# Sensor_Glove_Sensors-X02.net
KiCad netlist of a schematic drawn in Altium Designer
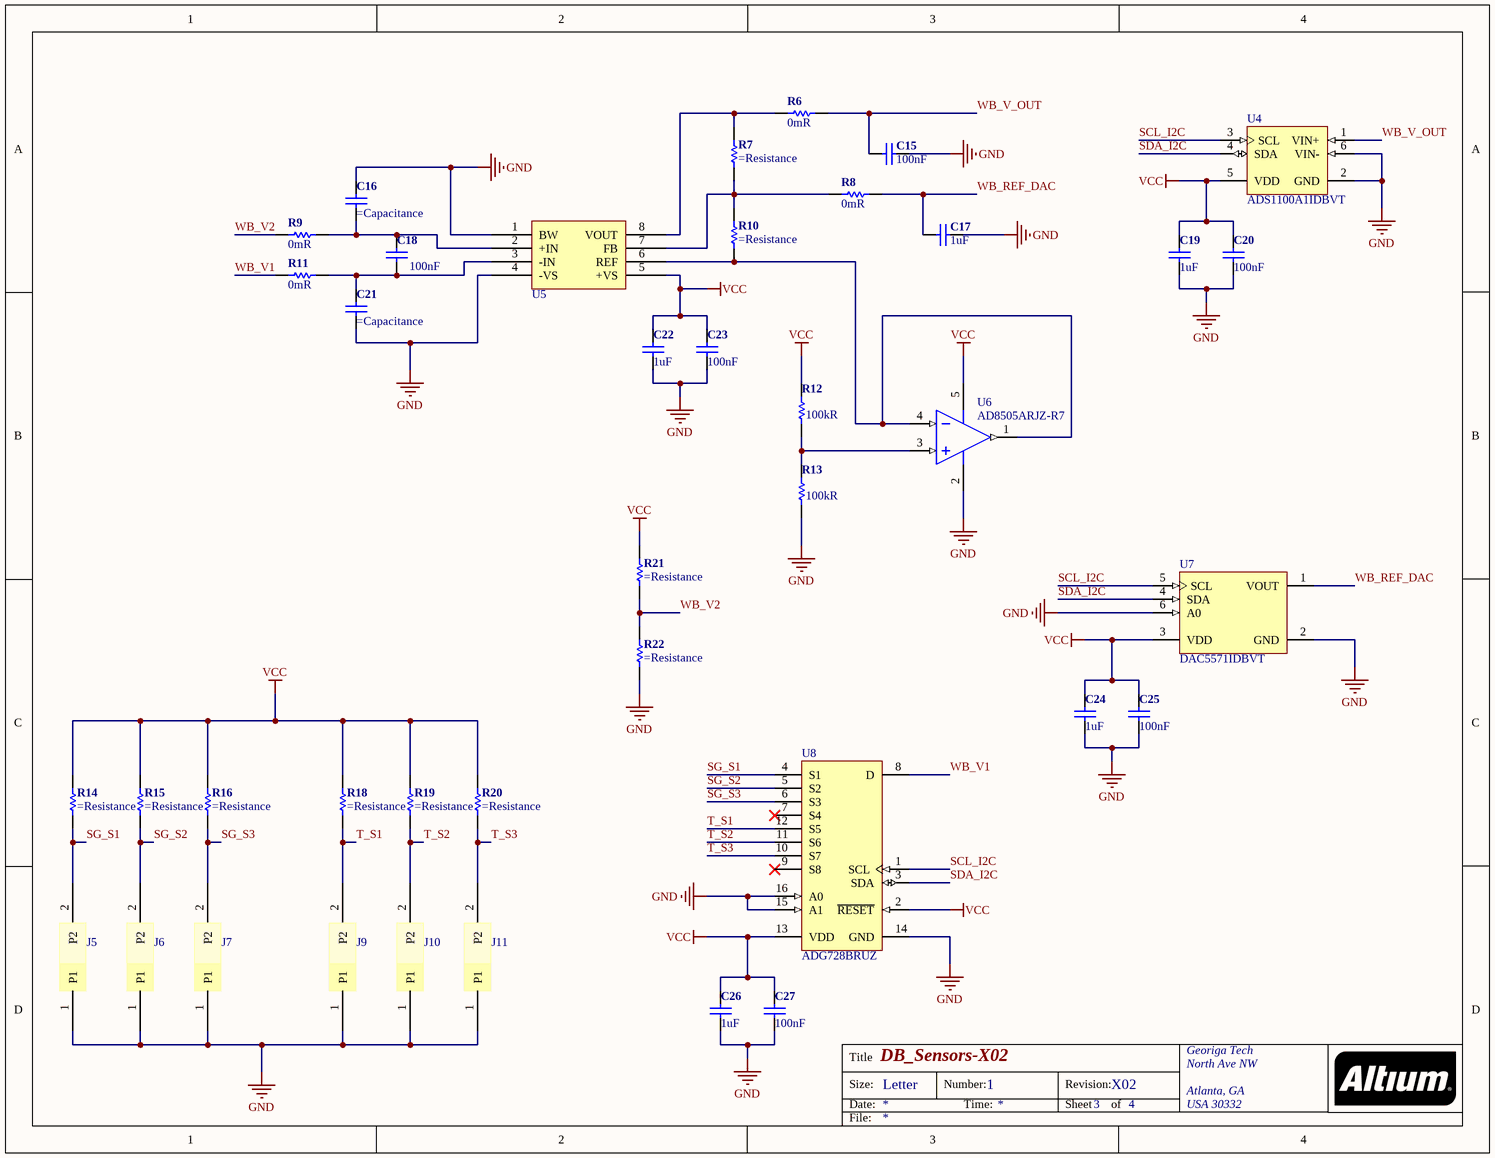
[diagram p0: Sensor_Glove_Sensors-X02.SchDoc]

(export (version "E")
  (design (tool "Eeschema 10.0.6"))
  (components
    (comp (ref "C15")
      (value "100nF")
      (footprint "C0402")
      (fields
        (field (name "MANUFACTURER") "Taiyo Yuden")
        (field (name "MANUFACTURER PART NUMBER") "TMK105BJ104KV-F")
        (field (name "TOLERANCE") "10%")
      )
      (libsource (lib "DB-X02") (part "C-0402(1005)"))
    )
    (comp (ref "C16")
      (value "~")
      (footprint "C0402")
      (description "___ OHM ___ mW 0402(1005) SMD")
      (libsource (lib "DB-X02") (part "C-0402(1005)"))
    )
    (comp (ref "C17")
      (value "1uF")
      (footprint "C0402")
      (fields
        (field (name "MANUFACTURER") "Yageo")
        (field (name "MANUFACTURER PART NUMBER") "CC0402MRX5R5BB105")
        (field (name "TOLERANCE") "20%")
      )
      (libsource (lib "DB-X02") (part "C-0402(1005)"))
    )
    (comp (ref "C18")
      (value "100nF")
      (footprint "C0402")
      (fields
        (field (name "MANUFACTURER") "Taiyo Yuden")
        (field (name "MANUFACTURER PART NUMBER") "TMK105BJ104KV-F")
        (field (name "TOLERANCE") "10%")
      )
      (libsource (lib "DB-X02") (part "C-0402(1005)"))
    )
    (comp (ref "C19")
      (value "1uF")
      (footprint "C0402")
      (fields
        (field (name "MANUFACTURER") "Yageo")
        (field (name "MANUFACTURER PART NUMBER") "CC0402MRX5R5BB105")
        (field (name "TOLERANCE") "20%")
      )
      (libsource (lib "DB-X02") (part "C-0402(1005)"))
    )
    (comp (ref "C20")
      (value "100nF")
      (footprint "C0402")
      (fields
        (field (name "MANUFACTURER") "Taiyo Yuden")
        (field (name "MANUFACTURER PART NUMBER") "TMK105BJ104KV-F")
        (field (name "TOLERANCE") "10%")
      )
      (libsource (lib "DB-X02") (part "C-0402(1005)"))
    )
    (comp (ref "C21")
      (value "~")
      (footprint "C0402")
      (description "___ OHM ___ mW 0402(1005) SMD")
      (libsource (lib "DB-X02") (part "C-0402(1005)"))
    )
    (comp (ref "C22")
      (value "1uF")
      (footprint "C0402")
      (fields
        (field (name "MANUFACTURER") "Yageo")
        (field (name "MANUFACTURER PART NUMBER") "CC0402MRX5R5BB105")
        (field (name "TOLERANCE") "20%")
      )
      (libsource (lib "DB-X02") (part "C-0402(1005)"))
    )
    (comp (ref "C23")
      (value "100nF")
      (footprint "C0402")
      (fields
        (field (name "MANUFACTURER") "Taiyo Yuden")
        (field (name "MANUFACTURER PART NUMBER") "TMK105BJ104KV-F")
        (field (name "TOLERANCE") "10%")
      )
      (libsource (lib "DB-X02") (part "C-0402(1005)"))
    )
    (comp (ref "C24")
      (value "1uF")
      (footprint "C0402")
      (fields
        (field (name "MANUFACTURER") "Yageo")
        (field (name "MANUFACTURER PART NUMBER") "CC0402MRX5R5BB105")
        (field (name "TOLERANCE") "20%")
      )
      (libsource (lib "DB-X02") (part "C-0402(1005)"))
    )
    (comp (ref "C25")
      (value "100nF")
      (footprint "C0402")
      (fields
        (field (name "MANUFACTURER") "Taiyo Yuden")
        (field (name "MANUFACTURER PART NUMBER") "TMK105BJ104KV-F")
        (field (name "TOLERANCE") "10%")
      )
      (libsource (lib "DB-X02") (part "C-0402(1005)"))
    )
    (comp (ref "C26")
      (value "1uF")
      (footprint "C0402")
      (fields
        (field (name "MANUFACTURER") "Yageo")
        (field (name "MANUFACTURER PART NUMBER") "CC0402MRX5R5BB105")
        (field (name "TOLERANCE") "20%")
      )
      (libsource (lib "DB-X02") (part "C-0402(1005)"))
    )
    (comp (ref "C27")
      (value "100nF")
      (footprint "C0402")
      (fields
        (field (name "MANUFACTURER") "Taiyo Yuden")
        (field (name "MANUFACTURER PART NUMBER") "TMK105BJ104KV-F")
        (field (name "TOLERANCE") "10%")
      )
      (libsource (lib "DB-X02") (part "C-0402(1005)"))
    )
    (comp (ref "J5")
      (value "Sensor Interconnect Pads")
      (footprint "Sensor_Interconnect_Pad")
      (description "Hole Pads for sensor interconnect solder pads")
      (libsource (lib "Sensor_Glove-X02") (part "Sensor_Interconnect"))
    )
    (comp (ref "J6")
      (value "Sensor Interconnect Pads")
      (footprint "Sensor_Interconnect_Pad")
      (description "Hole Pads for sensor interconnect solder pads")
      (libsource (lib "Sensor_Glove-X02") (part "Sensor_Interconnect"))
    )
    (comp (ref "J7")
      (value "Sensor Interconnect Pads")
      (footprint "Sensor_Interconnect_Pad")
      (description "Hole Pads for sensor interconnect solder pads")
      (libsource (lib "Sensor_Glove-X02") (part "Sensor_Interconnect"))
    )
    (comp (ref "J9")
      (value "Sensor Interconnect Pads")
      (footprint "Sensor_Interconnect_Pad")
      (description "Hole Pads for sensor interconnect solder pads")
      (libsource (lib "Sensor_Glove-X02") (part "Sensor_Interconnect"))
    )
    (comp (ref "J10")
      (value "Sensor Interconnect Pads")
      (footprint "Sensor_Interconnect_Pad")
      (description "Hole Pads for sensor interconnect solder pads")
      (libsource (lib "Sensor_Glove-X02") (part "Sensor_Interconnect"))
    )
    (comp (ref "J11")
      (value "Sensor Interconnect Pads")
      (footprint "Sensor_Interconnect_Pad")
      (description "Hole Pads for sensor interconnect solder pads")
      (libsource (lib "Sensor_Glove-X02") (part "Sensor_Interconnect"))
    )
    (comp (ref "R6")
      (value "0mR")
      (footprint "R0402")
      (description "Fixed Resistor, Metal Glaze/thick Film, 0.0625W, 0ohm, Surface Mount, 0402")
      (fields
        (field (name "MANUFACTURER") "Yageo")
        (field (name "MANUFACTURER PART NUMBER") "AC0402JR-070RL")
      )
      (libsource (lib "DB-X02") (part "R-0402(1005)"))
    )
    (comp (ref "R7")
      (value "~")
      (footprint "R0402")
      (description "___ OHM ___ mW 0402(1005) SMD")
      (libsource (lib "DB-X02") (part "R-0402(1005)"))
    )
    (comp (ref "R8")
      (value "0mR")
      (footprint "R0402")
      (description "Fixed Resistor, Metal Glaze/thick Film, 0.0625W, 0ohm, Surface Mount, 0402")
      (fields
        (field (name "MANUFACTURER") "Yageo")
        (field (name "MANUFACTURER PART NUMBER") "AC0402JR-070RL")
      )
      (libsource (lib "DB-X02") (part "R-0402(1005)"))
    )
    (comp (ref "R9")
      (value "0mR")
      (footprint "R0402")
      (description "Fixed Resistor, Metal Glaze/thick Film, 0.0625W, 0ohm, Surface Mount, 0402")
      (fields
        (field (name "MANUFACTURER") "Yageo")
        (field (name "MANUFACTURER PART NUMBER") "AC0402JR-070RL")
      )
      (libsource (lib "DB-X02") (part "R-0402(1005)"))
    )
    (comp (ref "R10")
      (value "~")
      (footprint "R0402")
      (description "___ OHM ___ mW 0402(1005) SMD")
      (libsource (lib "DB-X02") (part "R-0402(1005)"))
    )
    (comp (ref "R11")
      (value "0mR")
      (footprint "R0402")
      (description "Fixed Resistor, Metal Glaze/thick Film, 0.0625W, 0ohm, Surface Mount, 0402")
      (fields
        (field (name "MANUFACTURER") "Yageo")
        (field (name "MANUFACTURER PART NUMBER") "AC0402JR-070RL")
      )
      (libsource (lib "DB-X02") (part "R-0402(1005)"))
    )
    (comp (ref "R12")
      (value "100kR")
      (footprint "R0402")
      (fields
        (field (name "MANUFACTURER") "Yageo")
        (field (name "MANUFACTURER PART NUMBER") "AC0402FR-07100KL")
        (field (name "TOLERANCE") "1%")
      )
      (libsource (lib "DB-X02") (part "R-0402(1005)"))
    )
    (comp (ref "R13")
      (value "100kR")
      (footprint "R0402")
      (fields
        (field (name "MANUFACTURER") "Yageo")
        (field (name "MANUFACTURER PART NUMBER") "AC0402FR-07100KL")
        (field (name "TOLERANCE") "1%")
      )
      (libsource (lib "DB-X02") (part "R-0402(1005)"))
    )
    (comp (ref "R14")
      (value "~")
      (footprint "R0402")
      (description "___ OHM ___ mW 0402(1005) SMD")
      (libsource (lib "DB-X02") (part "R-0402(1005)"))
    )
    (comp (ref "R15")
      (value "~")
      (footprint "R0402")
      (description "___ OHM ___ mW 0402(1005) SMD")
      (libsource (lib "DB-X02") (part "R-0402(1005)"))
    )
    (comp (ref "R16")
      (value "~")
      (footprint "R0402")
      (description "___ OHM ___ mW 0402(1005) SMD")
      (libsource (lib "DB-X02") (part "R-0402(1005)"))
    )
    (comp (ref "R18")
      (value "~")
      (footprint "R0402")
      (description "___ OHM ___ mW 0402(1005) SMD")
      (libsource (lib "DB-X02") (part "R-0402(1005)"))
    )
    (comp (ref "R19")
      (value "~")
      (footprint "R0402")
      (description "___ OHM ___ mW 0402(1005) SMD")
      (libsource (lib "DB-X02") (part "R-0402(1005)"))
    )
    (comp (ref "R20")
      (value "~")
      (footprint "R0402")
      (description "___ OHM ___ mW 0402(1005) SMD")
      (libsource (lib "DB-X02") (part "R-0402(1005)"))
    )
    (comp (ref "R21")
      (value "~")
      (footprint "R0402")
      (description "___ OHM ___ mW 0402(1005) SMD")
      (libsource (lib "DB-X02") (part "R-0402(1005)"))
    )
    (comp (ref "R22")
      (value "~")
      (footprint "R0402")
      (description "___ OHM ___ mW 0402(1005) SMD")
      (libsource (lib "DB-X02") (part "R-0402(1005)"))
    )
    (comp (ref "U4")
      (value "ADS1100A1IDBVT")
      (footprint "TI-DBV6_N")
      (description "Self-Calibrating, 16-Bit ADC, -40 to 85 degC, 6-pin SOT23 (DBV6), Green (RoHS & no Sb/Br)")
      (fields (field (name "MANUFACTURER") "Texas Instruments"))
      (libsource (lib "Altium Content Vault") (part "TI-ADS1XX0XDBV6"))
    )
    (comp (ref "U5")
      (value "Instrumentation Amplifier")
      (footprint "8-MSOP")
      (description "Instrumentation Amplifier, 1 Func, 75uV Offset-Max, 0.2MHz Band Width, CMOS, PDSO8")
      (fields
        (field (name "MANUFACTURER") "Analog Devices")
        (field (name "MANUFACTURER PART NUMBER") "AD8237ARMZ-R7")
      )
      (libsource (lib "DB-X02") (part "AD8237"))
    )
    (comp (ref "U6")
      (value "AD8505ARJZ-R7")
      (footprint "ADI-RJ-5_N")
      (fields (field (name "MANUFACTURER") "Analog Devices"))
      (libsource (lib "Altium Content Vault") (part "ADI-ADxxxx-X-5"))
    )
    (comp (ref "U7")
      (value "DAC5571IDBVT")
      (footprint "TI-DBV6_M")
      (fields (field (name "MANUFACTURER") "Texas Instruments"))
      (libsource (lib "Altium Content Vault") (part "TI-DACX571DBV6"))
    )
    (comp (ref "U8")
      (value "ADG728BRUZ")
      (footprint "ADI-RU-16_M")
      (fields (field (name "MANUFACTURER") "Analog Devices"))
      (libsource (lib "Altium Content Vault") (part "ADI-ADG728-RU-16"))
    )
  )
  (nets
    (net (code "1") (name "/SCL_I2C") (class "Default")
      (node (ref "U4") (pin "3") (pinfunction "SCL_3") (pintype "input"))
      (node (ref "U7") (pin "5") (pinfunction "SCL_5") (pintype "input"))
      (node (ref "U8") (pin "1") (pinfunction "SCL_1") (pintype "input"))
    )
    (net (code "2") (name "/SDA_I2C") (class "Default")
      (node (ref "U4") (pin "4") (pinfunction "SDA_4") (pintype "bidirectional"))
      (node (ref "U7") (pin "4") (pinfunction "SDA_4") (pintype "input"))
      (node (ref "U8") (pin "3") (pinfunction "SDA_3") (pintype "bidirectional"))
    )
    (net (code "3") (name "/SG_S1") (class "Default")
      (node (ref "J5") (pin "2") (pinfunction "P2_2") (pintype "passive"))
      (node (ref "R14") (pin "2") (pinfunction "2_2") (pintype "passive"))
      (node (ref "U8") (pin "4") (pinfunction "S1_4") (pintype "passive"))
    )
    (net (code "4") (name "/SG_S2") (class "Default")
      (node (ref "J6") (pin "2") (pinfunction "P2_2") (pintype "passive"))
      (node (ref "R15") (pin "2") (pinfunction "2_2") (pintype "passive"))
      (node (ref "U8") (pin "5") (pinfunction "S2_5") (pintype "passive"))
    )
    (net (code "5") (name "/SG_S3") (class "Default")
      (node (ref "J7") (pin "2") (pinfunction "P2_2") (pintype "passive"))
      (node (ref "R16") (pin "2") (pinfunction "2_2") (pintype "passive"))
      (node (ref "U8") (pin "6") (pinfunction "S3_6") (pintype "passive"))
    )
    (net (code "6") (name "/T_S1") (class "Default")
      (node (ref "J9") (pin "2") (pinfunction "P2_2") (pintype "passive"))
      (node (ref "R18") (pin "2") (pinfunction "2_2") (pintype "passive"))
      (node (ref "U8") (pin "12") (pinfunction "S5_12") (pintype "passive"))
    )
    (net (code "7") (name "/T_S2") (class "Default")
      (node (ref "J10") (pin "2") (pinfunction "P2_2") (pintype "passive"))
      (node (ref "R19") (pin "2") (pinfunction "2_2") (pintype "passive"))
      (node (ref "U8") (pin "11") (pinfunction "S6_11") (pintype "passive"))
    )
    (net (code "8") (name "/T_S3") (class "Default")
      (node (ref "J11") (pin "2") (pinfunction "P2_2") (pintype "passive"))
      (node (ref "R20") (pin "2") (pinfunction "2_2") (pintype "passive"))
      (node (ref "U8") (pin "10") (pinfunction "S7_10") (pintype "passive"))
    )
    (net (code "9") (name "/WB_REF_DAC") (class "Default")
      (node (ref "C17") (pin "1") (pinfunction "1_1") (pintype "passive"))
      (node (ref "R8") (pin "2") (pinfunction "2_2") (pintype "passive"))
      (node (ref "U7") (pin "1") (pinfunction "VOUT_1") (pintype "tri_state"))
    )
    (net (code "10") (name "/WB_V1") (class "Default")
      (node (ref "R11") (pin "1") (pinfunction "1_1") (pintype "passive"))
      (node (ref "U8") (pin "8") (pinfunction "D_8") (pintype "passive"))
    )
    (net (code "11") (name "/WB_V2") (class "Default")
      (node (ref "R21") (pin "2") (pinfunction "2_2") (pintype "passive"))
      (node (ref "R22") (pin "1") (pinfunction "1_1") (pintype "passive"))
      (node (ref "R9") (pin "1") (pinfunction "1_1") (pintype "passive"))
    )
    (net (code "12") (name "/WB_V_OUT") (class "Default")
      (node (ref "C15") (pin "1") (pinfunction "1_1") (pintype "passive"))
      (node (ref "R6") (pin "2") (pinfunction "2_2") (pintype "passive"))
      (node (ref "U4") (pin "1") (pinfunction "VIN+_1") (pintype "input"))
    )
    (net (code "13") (name "GND") (class "Default")
      (node (ref "C15") (pin "2") (pinfunction "2_2") (pintype "passive"))
      (node (ref "C16") (pin "1") (pinfunction "1_1") (pintype "passive"))
      (node (ref "C17") (pin "2") (pinfunction "2_2") (pintype "passive"))
      (node (ref "C19") (pin "2") (pinfunction "2_2") (pintype "passive"))
      (node (ref "C20") (pin "2") (pinfunction "2_2") (pintype "passive"))
      (node (ref "C21") (pin "2") (pinfunction "2_2") (pintype "passive"))
      (node (ref "C22") (pin "2") (pinfunction "2_2") (pintype "passive"))
      (node (ref "C23") (pin "2") (pinfunction "2_2") (pintype "passive"))
      (node (ref "C24") (pin "2") (pinfunction "2_2") (pintype "passive"))
      (node (ref "C25") (pin "2") (pinfunction "2_2") (pintype "passive"))
      (node (ref "C26") (pin "2") (pinfunction "2_2") (pintype "passive"))
      (node (ref "C27") (pin "2") (pinfunction "2_2") (pintype "passive"))
      (node (ref "J10") (pin "1") (pinfunction "P1_1") (pintype "passive"))
      (node (ref "J11") (pin "1") (pinfunction "P1_1") (pintype "passive"))
      (node (ref "J5") (pin "1") (pinfunction "P1_1") (pintype "passive"))
      (node (ref "J6") (pin "1") (pinfunction "P1_1") (pintype "passive"))
      (node (ref "J7") (pin "1") (pinfunction "P1_1") (pintype "passive"))
      (node (ref "J9") (pin "1") (pinfunction "P1_1") (pintype "passive"))
      (node (ref "R13") (pin "2") (pinfunction "2_2") (pintype "passive"))
      (node (ref "R22") (pin "2") (pinfunction "2_2") (pintype "passive"))
      (node (ref "U4") (pin "2") (pinfunction "GND_2") (pintype "power_in"))
      (node (ref "U4") (pin "6") (pinfunction "VIN-_6") (pintype "input"))
      (node (ref "U5") (pin "1") (pinfunction "BW_1") (pintype "passive"))
      (node (ref "U5") (pin "4") (pinfunction "-VS_4") (pintype "passive"))
      (node (ref "U6") (pin "2") (pinfunction "-V_2") (pintype "power_in"))
      (node (ref "U7") (pin "2") (pinfunction "GND_2") (pintype "power_in"))
      (node (ref "U7") (pin "6") (pinfunction "A0_6") (pintype "input"))
      (node (ref "U8") (pin "14") (pinfunction "GND_14") (pintype "power_in"))
      (node (ref "U8") (pin "15") (pinfunction "A1_15") (pintype "input"))
      (node (ref "U8") (pin "16") (pinfunction "A0_16") (pintype "input"))
    )
    (net (code "14") (name "Net-(U5-+IN)") (class "Default")
      (node (ref "C16") (pin "2") (pinfunction "2_2") (pintype "passive"))
      (node (ref "C18") (pin "1") (pinfunction "1_1") (pintype "passive"))
      (node (ref "R9") (pin "2") (pinfunction "2_2") (pintype "passive"))
      (node (ref "U5") (pin "2") (pinfunction "+IN_2") (pintype "passive"))
    )
    (net (code "15") (name "Net-(U5--IN)") (class "Default")
      (node (ref "C18") (pin "2") (pinfunction "2_2") (pintype "passive"))
      (node (ref "C21") (pin "1") (pinfunction "1_1") (pintype "passive"))
      (node (ref "R11") (pin "2") (pinfunction "2_2") (pintype "passive"))
      (node (ref "U5") (pin "3") (pinfunction "-IN_3") (pintype "passive"))
    )
    (net (code "16") (name "Net-(U5-FB)") (class "Default")
      (node (ref "R10") (pin "2") (pinfunction "2_2") (pintype "passive"))
      (node (ref "R7") (pin "1") (pinfunction "1_1") (pintype "passive"))
      (node (ref "R8") (pin "1") (pinfunction "1_1") (pintype "passive"))
      (node (ref "U5") (pin "7") (pinfunction "FB_7") (pintype "passive"))
    )
    (net (code "17") (name "Net-(U5-REF)") (class "Default")
      (node (ref "R10") (pin "1") (pinfunction "1_1") (pintype "passive"))
      (node (ref "U5") (pin "6") (pinfunction "REF_6") (pintype "passive"))
      (node (ref "U6") (pin "1") (pinfunction "OUT_1") (pintype "output"))
      (node (ref "U6") (pin "4") (pinfunction "-IN_4") (pintype "input"))
    )
    (net (code "18") (name "Net-(U5-VOUT)") (class "Default")
      (node (ref "R6") (pin "1") (pinfunction "1_1") (pintype "passive"))
      (node (ref "R7") (pin "2") (pinfunction "2_2") (pintype "passive"))
      (node (ref "U5") (pin "8") (pinfunction "VOUT_8") (pintype "passive"))
    )
    (net (code "19") (name "Net-(U6-+IN)") (class "Default")
      (node (ref "R12") (pin "2") (pinfunction "2_2") (pintype "passive"))
      (node (ref "R13") (pin "1") (pinfunction "1_1") (pintype "passive"))
      (node (ref "U6") (pin "3") (pinfunction "+IN_3") (pintype "input"))
    )
    (net (code "20") (name "VCC") (class "Default")
      (node (ref "C19") (pin "1") (pinfunction "1_1") (pintype "passive"))
      (node (ref "C20") (pin "1") (pinfunction "1_1") (pintype "passive"))
      (node (ref "C22") (pin "1") (pinfunction "1_1") (pintype "passive"))
      (node (ref "C23") (pin "1") (pinfunction "1_1") (pintype "passive"))
      (node (ref "C24") (pin "1") (pinfunction "1_1") (pintype "passive"))
      (node (ref "C25") (pin "1") (pinfunction "1_1") (pintype "passive"))
      (node (ref "C26") (pin "1") (pinfunction "1_1") (pintype "passive"))
      (node (ref "C27") (pin "1") (pinfunction "1_1") (pintype "passive"))
      (node (ref "R12") (pin "1") (pinfunction "1_1") (pintype "passive"))
      (node (ref "R14") (pin "1") (pinfunction "1_1") (pintype "passive"))
      (node (ref "R15") (pin "1") (pinfunction "1_1") (pintype "passive"))
      (node (ref "R16") (pin "1") (pinfunction "1_1") (pintype "passive"))
      (node (ref "R18") (pin "1") (pinfunction "1_1") (pintype "passive"))
      (node (ref "R19") (pin "1") (pinfunction "1_1") (pintype "passive"))
      (node (ref "R20") (pin "1") (pinfunction "1_1") (pintype "passive"))
      (node (ref "R21") (pin "1") (pinfunction "1_1") (pintype "passive"))
      (node (ref "U4") (pin "5") (pinfunction "VDD_5") (pintype "power_in"))
      (node (ref "U5") (pin "5") (pinfunction "+VS_5") (pintype "passive"))
      (node (ref "U6") (pin "5") (pinfunction "+V_5") (pintype "power_in"))
      (node (ref "U7") (pin "3") (pinfunction "VDD_3") (pintype "power_in"))
      (node (ref "U8") (pin "13") (pinfunction "VDD_13") (pintype "power_in"))
      (node (ref "U8") (pin "2") (pinfunction "~{RESET}_2") (pintype "input"))
    )
    (net (code "21") (name "unconnected-(U8-S4-Pad7)") (class "Default")
      (node (ref "U8") (pin "7") (pinfunction "S4_7") (pintype "passive+no_connect"))
    )
    (net (code "22") (name "unconnected-(U8-S8-Pad9)") (class "Default")
      (node (ref "U8") (pin "9") (pinfunction "S8_9") (pintype "passive+no_connect"))
    )
  )
)
